# MPU-Peripherals.net
KiCad netlist of a schematic drawn in Altium Designer
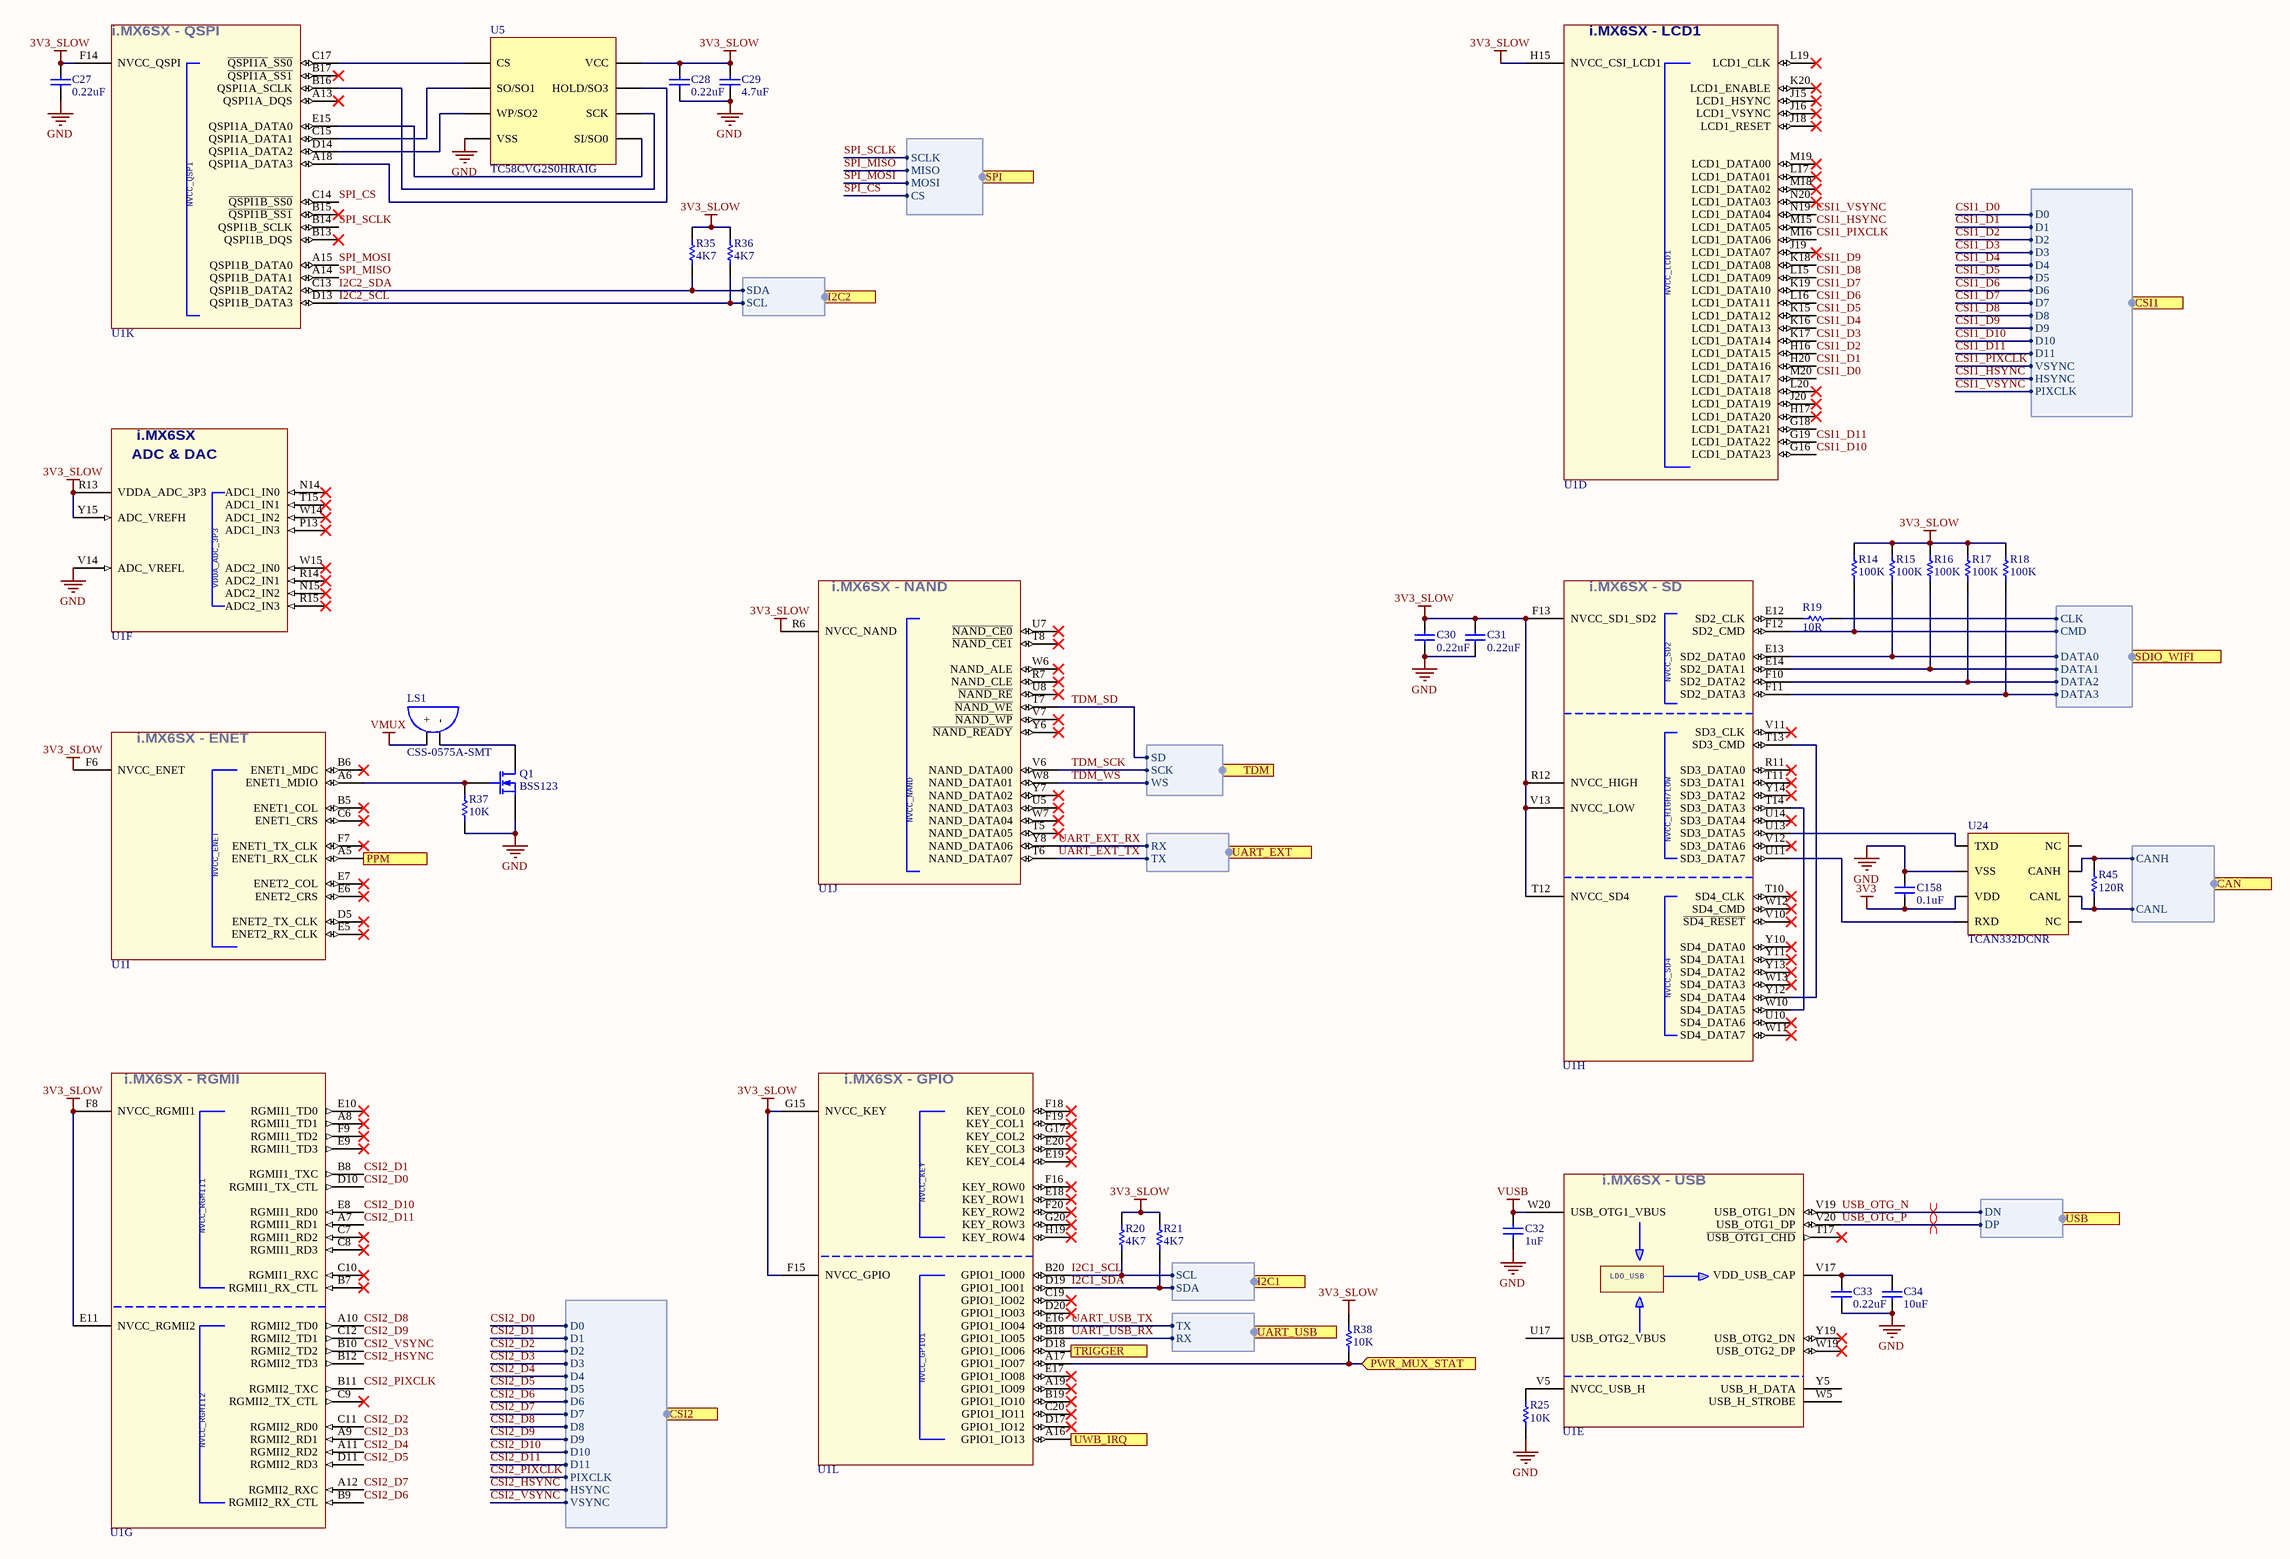
[diagram p0: MPU-Peripherals.SchDoc]

(export (version "E")
  (design (tool "Eeschema 10.0.6"))
  (components
    (comp (ref "C27")
      (value "0.22uF")
      (footprint "C0402[1005X55]")
      (description "0.22uF 6.3V 10% 0402 (1005 Metric)")
      (fields (field (name "PARTNUMBER") "JMK105BJ224KV-F") (field (name "MANUFACTURER") "Taiyo Yuden"))
      (libsource (lib "Capacitors") (part "CAP_0.22uF_6.3V_0402_10%"))
    )
    (comp (ref "C28")
      (value "0.22uF")
      (footprint "C0402[1005X55]")
      (description "0.22uF 6.3V 10% 0402 (1005 Metric)")
      (fields (field (name "PARTNUMBER") "JMK105BJ224KV-F") (field (name "MANUFACTURER") "Taiyo Yuden"))
      (libsource (lib "Capacitors") (part "CAP_0.22uF_6.3V_0402_10%"))
    )
    (comp (ref "C29")
      (value "4.7uF")
      (footprint "C0402[1005X55]")
      (description "4.7uF 6.3V 20% 0402 (1005 Metric)")
      (fields (field (name "PARTNUMBER") "GRM155R60J475ME47D") (field (name "MANUFACTURER") "Murata"))
      (libsource (lib "Capacitors") (part "CAP_4.7uF_6.3V_0402_20%"))
    )
    (comp (ref "C30")
      (value "0.22uF")
      (footprint "C0402[1005X55]")
      (description "0.22uF 6.3V 10% 0402 (1005 Metric)")
      (fields (field (name "PARTNUMBER") "JMK105BJ224KV-F") (field (name "MANUFACTURER") "Taiyo Yuden"))
      (libsource (lib "Capacitors") (part "CAP_0.22uF_6.3V_0402_10%"))
    )
    (comp (ref "C31")
      (value "0.22uF")
      (footprint "C0402[1005X55]")
      (description "0.22uF 6.3V 10% 0402 (1005 Metric)")
      (fields (field (name "PARTNUMBER") "JMK105BJ224KV-F") (field (name "MANUFACTURER") "Taiyo Yuden"))
      (libsource (lib "Capacitors") (part "CAP_0.22uF_6.3V_0402_10%"))
    )
    (comp (ref "C32")
      (value "1uF")
      (footprint "C0402[1005X55]")
      (description "1uF 16V 10% 0402 (1005 Metric)")
      (fields (field (name "PARTNUMBER") "GRM155R61C105KE01D") (field (name "MANUFACTURER") "Murata"))
      (libsource (lib "Capacitors") (part "CAP_1uF_16V_0402_10%"))
    )
    (comp (ref "C33")
      (value "0.22uF")
      (footprint "C0402[1005X55]")
      (description "0.22uF 6.3V 10% 0402 (1005 Metric)")
      (fields (field (name "PARTNUMBER") "JMK105BJ224KV-F") (field (name "MANUFACTURER") "Taiyo Yuden"))
      (libsource (lib "Capacitors") (part "CAP_0.22uF_6.3V_0402_10%"))
    )
    (comp (ref "C34")
      (value "10uF")
      (footprint "C0402[1005X55]")
      (description "10uF 6.3V 20% 0402 (1005 Metric)")
      (fields (field (name "PARTNUMBER") "GRM155R60J106ME44D") (field (name "MANUFACTURER") "Murata"))
      (libsource (lib "Capacitors") (part "CAP_10uF_6.3V_0402_20%"))
    )
    (comp (ref "C158")
      (value "0.1uF")
      (footprint "C0402[1005X55]")
      (description "0.1uF 6.3V 10% 0402 (1005 Metric)")
      (fields (field (name "PARTNUMBER") "GRM155R70J104KA01D") (field (name "MANUFACTURER") "Murata"))
      (libsource (lib "Capacitors") (part "CAP_0.1uF_6.3V_0402_10%"))
    )
    (comp (ref "LS1")
      (value "CSS-0575A-SMT")
      (footprint "CSS-0575A-SMT")
      (description "Magnetic Buzzer Transducer")
      (fields (field (name "MANUFACTURER") "CUI, Inc."))
      (libsource (lib "Components") (part "CSS-0575A-SMT"))
    )
    (comp (ref "Q1")
      (value "BSS123")
      (footprint "SOT323-3")
      (description "N-Channel MOSFET")
      (fields (field (name "PARTNUMBER") "BSS123WQ-7-F") (field (name "MANUFACTURER") "Diodes Incorporated"))
      (libsource (lib "MOSFETs") (part "BSS123WQ-7-F"))
    )
    (comp (ref "R14")
      (value "100K")
      (footprint "R0402[1005]")
      (description "100K 0.063W 1% 0402 (1005 Metric)")
      (fields (field (name "MANUFACTURER") "KOA Speer") (field (name "PARTNUMBER") "RK73H1ETTP1003F"))
      (libsource (lib "Resistors") (part "RES_100K_0402_1%"))
    )
    (comp (ref "R15")
      (value "100K")
      (footprint "R0402[1005]")
      (description "100K 0.063W 1% 0402 (1005 Metric)")
      (fields (field (name "MANUFACTURER") "KOA Speer") (field (name "PARTNUMBER") "RK73H1ETTP1003F"))
      (libsource (lib "Resistors") (part "RES_100K_0402_1%"))
    )
    (comp (ref "R16")
      (value "100K")
      (footprint "R0402[1005]")
      (description "100K 0.063W 1% 0402 (1005 Metric)")
      (fields (field (name "MANUFACTURER") "KOA Speer") (field (name "PARTNUMBER") "RK73H1ETTP1003F"))
      (libsource (lib "Resistors") (part "RES_100K_0402_1%"))
    )
    (comp (ref "R17")
      (value "100K")
      (footprint "R0402[1005]")
      (description "100K 0.063W 1% 0402 (1005 Metric)")
      (fields (field (name "MANUFACTURER") "KOA Speer") (field (name "PARTNUMBER") "RK73H1ETTP1003F"))
      (libsource (lib "Resistors") (part "RES_100K_0402_1%"))
    )
    (comp (ref "R18")
      (value "100K")
      (footprint "R0402[1005]")
      (description "100K 0.063W 1% 0402 (1005 Metric)")
      (fields (field (name "MANUFACTURER") "KOA Speer") (field (name "PARTNUMBER") "RK73H1ETTP1003F"))
      (libsource (lib "Resistors") (part "RES_100K_0402_1%"))
    )
    (comp (ref "R19")
      (value "10R")
      (footprint "R0402[1005]")
      (description "10R 0.063W 1% 0402 (1005 Metric)")
      (fields (field (name "MANUFACTURER") "KOA Speer") (field (name "PARTNUMBER") "RK73H1ETTP10R0F"))
      (libsource (lib "Resistors") (part "RES_10R_0402_1%"))
    )
    (comp (ref "R20")
      (value "4K7")
      (footprint "R0402[1005]")
      (description "4K7 0.063W 1% 0402 (1005 Metric)")
      (fields (field (name "MANUFACTURER") "KOA Speer") (field (name "PARTNUMBER") "RK73H1ETTP4701F"))
      (libsource (lib "Resistors") (part "RES_4K7_0402_1%"))
    )
    (comp (ref "R21")
      (value "4K7")
      (footprint "R0402[1005]")
      (description "4K7 0.063W 1% 0402 (1005 Metric)")
      (fields (field (name "MANUFACTURER") "KOA Speer") (field (name "PARTNUMBER") "RK73H1ETTP4701F"))
      (libsource (lib "Resistors") (part "RES_4K7_0402_1%"))
    )
    (comp (ref "R25")
      (value "10K")
      (footprint "R0402[1005]")
      (description "10K 0.063W 1% 0402 (1005 Metric)")
      (fields (field (name "MANUFACTURER") "KOA Speer") (field (name "PARTNUMBER") "RK73H1ETTP1002F"))
      (libsource (lib "Resistors") (part "RES_10K_0402_1%"))
    )
    (comp (ref "R35")
      (value "4K7")
      (footprint "R0402[1005]")
      (description "4K7 0.063W 1% 0402 (1005 Metric)")
      (fields (field (name "MANUFACTURER") "KOA Speer") (field (name "PARTNUMBER") "RK73H1ETTP4701F"))
      (libsource (lib "Resistors") (part "RES_4K7_0402_1%"))
    )
    (comp (ref "R36")
      (value "4K7")
      (footprint "R0402[1005]")
      (description "4K7 0.063W 1% 0402 (1005 Metric)")
      (fields (field (name "MANUFACTURER") "KOA Speer") (field (name "PARTNUMBER") "RK73H1ETTP4701F"))
      (libsource (lib "Resistors") (part "RES_4K7_0402_1%"))
    )
    (comp (ref "R37")
      (value "10K")
      (footprint "R0402[1005]")
      (description "10K 0.063W 1% 0402 (1005 Metric)")
      (fields (field (name "MANUFACTURER") "KOA Speer") (field (name "PARTNUMBER") "RK73H1ETTP1002F"))
      (libsource (lib "Resistors") (part "RES_10K_0402_1%"))
    )
    (comp (ref "R38")
      (value "10K")
      (footprint "R0402[1005]")
      (description "10K 0.063W 1% 0402 (1005 Metric)")
      (fields (field (name "MANUFACTURER") "KOA Speer") (field (name "PARTNUMBER") "RK73H1ETTP1002F"))
      (libsource (lib "Resistors") (part "RES_10K_0402_1%"))
    )
    (comp (ref "R45")
      (value "120R")
      (footprint "R0402[1005]")
      (description "120R 0.063W 1% 0402 (1005 Metric)")
      (fields (field (name "MANUFACTURER") "KOA Speer") (field (name "PARTNUMBER") "RK73H1ETTP1200F"))
      (libsource (lib "Resistors") (part "RES_120R_0402_1%"))
    )
    (comp (ref "U1")
      (value "MCIMX6X3EVO10AB")
      (footprint "BGA-400")
      (description "IC MPU I.MX6SX 1GHZ 400MAPBGA")
      (fields (field (name "MANUFACTURER") "NXP"))
      (libsource (lib "ICs") (part "MCIMX6X3EVO10AB"))
    )
    (comp (ref "U5")
      (value "TC58CVG2S0HRAIG")
      (footprint "WSON-8 (6X8MM)")
      (description "IC FLASH 4G SPI 104MHZ 8WSON")
      (fields (field (name "MANUFACTURER") "Toshiba Memory America, Inc."))
      (libsource (lib "ICs") (part "TC58CVG2S0HRAIG"))
    )
    (comp (ref "U24")
      (value "TCAN332DCNR")
      (footprint "SOT-23-8")
      (description "CAN Interface IC 3.3-V CAN Transceivers with CAN FD (Flexible Data Rate) 8-SOT-23 -40 to 125")
      (fields (field (name "MANUFACTURER") "Texas Instruments"))
      (libsource (lib "ICs") (part "TCAN332DCNR"))
    )
  )
  (nets
    (net (code "9") (name "/CANH") (class "Default")
      (node (ref "R45") (pin "2") (pinfunction "2_2") (pintype "passive"))
      (node (ref "U24") (pin "7") (pinfunction "CANH_7") (pintype "passive"))
    )
    (net (code "10") (name "/CANL") (class "Default")
      (node (ref "R45") (pin "1") (pinfunction "1_1") (pintype "passive"))
      (node (ref "U24") (pin "6") (pinfunction "CANL_6") (pintype "passive"))
    )
    (net (code "11") (name "/CLK") (class "Default")
      (node (ref "R19") (pin "2") (pinfunction "2_2") (pintype "passive"))
    )
    (net (code "12") (name "/CMD") (class "Default")
      (node (ref "R14") (pin "1") (pinfunction "1_1") (pintype "passive"))
      (node (ref "U1") (pin "F12") (pinfunction "SD2_CMD_F12") (pintype "bidirectional"))
    )
    (net (code "13") (name "/CSI1_D0") (class "Default")
      (node (ref "U1") (pin "M20") (pinfunction "LCD1_DATA17_M20") (pintype "bidirectional"))
    )
    (net (code "14") (name "/CSI1_D1") (class "Default")
      (node (ref "U1") (pin "H20") (pinfunction "LCD1_DATA16_H20") (pintype "bidirectional"))
    )
    (net (code "15") (name "/CSI1_D2") (class "Default")
      (node (ref "U1") (pin "H16") (pinfunction "LCD1_DATA15_H16") (pintype "bidirectional"))
    )
    (net (code "16") (name "/CSI1_D3") (class "Default")
      (node (ref "U1") (pin "K17") (pinfunction "LCD1_DATA14_K17") (pintype "bidirectional"))
    )
    (net (code "17") (name "/CSI1_D4") (class "Default")
      (node (ref "U1") (pin "K16") (pinfunction "LCD1_DATA13_K16") (pintype "bidirectional"))
    )
    (net (code "18") (name "/CSI1_D5") (class "Default")
      (node (ref "U1") (pin "K15") (pinfunction "LCD1_DATA12_K15") (pintype "bidirectional"))
    )
    (net (code "19") (name "/CSI1_D6") (class "Default")
      (node (ref "U1") (pin "L16") (pinfunction "LCD1_DATA11_L16") (pintype "bidirectional"))
    )
    (net (code "20") (name "/CSI1_D7") (class "Default")
      (node (ref "U1") (pin "K19") (pinfunction "LCD1_DATA10_K19") (pintype "bidirectional"))
    )
    (net (code "21") (name "/CSI1_D8") (class "Default")
      (node (ref "U1") (pin "L15") (pinfunction "LCD1_DATA09_L15") (pintype "bidirectional"))
    )
    (net (code "22") (name "/CSI1_D9") (class "Default")
      (node (ref "U1") (pin "K18") (pinfunction "LCD1_DATA08_K18") (pintype "bidirectional"))
    )
    (net (code "23") (name "/CSI1_D10") (class "Default")
      (node (ref "U1") (pin "G16") (pinfunction "LCD1_DATA23_G16") (pintype "bidirectional"))
    )
    (net (code "24") (name "/CSI1_D11") (class "Default")
      (node (ref "U1") (pin "G19") (pinfunction "LCD1_DATA22_G19") (pintype "bidirectional"))
    )
    (net (code "25") (name "/CSI1_HSYNC") (class "Default")
      (node (ref "U1") (pin "M15") (pinfunction "LCD1_DATA05_M15") (pintype "bidirectional"))
    )
    (net (code "26") (name "/CSI1_PIXCLK") (class "Default")
      (node (ref "U1") (pin "M16") (pinfunction "LCD1_DATA06_M16") (pintype "bidirectional"))
    )
    (net (code "27") (name "/CSI1_VSYNC") (class "Default")
      (node (ref "U1") (pin "N19") (pinfunction "LCD1_DATA04_N19") (pintype "bidirectional"))
    )
    (net (code "28") (name "/CSI2_D0") (class "Default")
      (node (ref "U1") (pin "D10") (pinfunction "RGMII1_TX_CTL_D10") (pintype "output"))
    )
    (net (code "29") (name "/CSI2_D1") (class "Default")
      (node (ref "U1") (pin "B8") (pinfunction "RGMII1_TXC_B8") (pintype "output"))
    )
    (net (code "30") (name "/CSI2_D2") (class "Default")
      (node (ref "U1") (pin "C11") (pinfunction "RGMII2_RD0_C11") (pintype "input"))
    )
    (net (code "31") (name "/CSI2_D3") (class "Default")
      (node (ref "U1") (pin "A9") (pinfunction "RGMII2_RD1_A9") (pintype "input"))
    )
    (net (code "32") (name "/CSI2_D4") (class "Default")
      (node (ref "U1") (pin "A11") (pinfunction "RGMII2_RD2_A11") (pintype "input"))
    )
    (net (code "33") (name "/CSI2_D5") (class "Default")
      (node (ref "U1") (pin "D11") (pinfunction "RGMII2_RD3_D11") (pintype "input"))
    )
    (net (code "34") (name "/CSI2_D6") (class "Default")
      (node (ref "U1") (pin "B9") (pinfunction "RGMII2_RX_CTL_B9") (pintype "input"))
    )
    (net (code "35") (name "/CSI2_D7") (class "Default")
      (node (ref "U1") (pin "A12") (pinfunction "RGMII2_RXC_A12") (pintype "input"))
    )
    (net (code "36") (name "/CSI2_D8") (class "Default")
      (node (ref "U1") (pin "A10") (pinfunction "RGMII2_TD0_A10") (pintype "output"))
    )
    (net (code "37") (name "/CSI2_D9") (class "Default")
      (node (ref "U1") (pin "C12") (pinfunction "RGMII2_TD1_C12") (pintype "output"))
    )
    (net (code "38") (name "/CSI2_D10") (class "Default")
      (node (ref "U1") (pin "E8") (pinfunction "RGMII1_RD0_E8") (pintype "input"))
    )
    (net (code "39") (name "/CSI2_D11") (class "Default")
      (node (ref "U1") (pin "A7") (pinfunction "RGMII1_RD1_A7") (pintype "input"))
    )
    (net (code "40") (name "/CSI2_HSYNC") (class "Default")
      (node (ref "U1") (pin "B12") (pinfunction "RGMII2_TD3_B12") (pintype "output"))
    )
    (net (code "41") (name "/CSI2_PIXCLK") (class "Default")
      (node (ref "U1") (pin "B11") (pinfunction "RGMII2_TXC_B11") (pintype "output"))
    )
    (net (code "42") (name "/CSI2_VSYNC") (class "Default")
      (node (ref "U1") (pin "B10") (pinfunction "RGMII2_TD2_B10") (pintype "output"))
    )
    (net (code "43") (name "/DATA0") (class "Default")
      (node (ref "R15") (pin "1") (pinfunction "1_1") (pintype "passive"))
      (node (ref "U1") (pin "E13") (pinfunction "SD2_DATA0_E13") (pintype "bidirectional"))
    )
    (net (code "44") (name "/DATA1") (class "Default")
      (node (ref "R16") (pin "1") (pinfunction "1_1") (pintype "passive"))
      (node (ref "U1") (pin "E14") (pinfunction "SD2_DATA1_E14") (pintype "bidirectional"))
    )
    (net (code "45") (name "/DATA2") (class "Default")
      (node (ref "R17") (pin "1") (pinfunction "1_1") (pintype "passive"))
      (node (ref "U1") (pin "F10") (pinfunction "SD2_DATA2_F10") (pintype "bidirectional"))
    )
    (net (code "46") (name "/DATA3") (class "Default")
      (node (ref "R18") (pin "1") (pinfunction "1_1") (pintype "passive"))
      (node (ref "U1") (pin "F11") (pinfunction "SD2_DATA3_F11") (pintype "bidirectional"))
    )
    (net (code "47") (name "/I2C1_SCL") (class "Default")
      (node (ref "R20") (pin "1") (pinfunction "1_1") (pintype "passive"))
      (node (ref "U1") (pin "B20") (pinfunction "GPIO1_IO00_B20") (pintype "bidirectional"))
    )
    (net (code "48") (name "/I2C1_SDA") (class "Default")
      (node (ref "R21") (pin "1") (pinfunction "1_1") (pintype "passive"))
      (node (ref "U1") (pin "D19") (pinfunction "GPIO1_IO01_D19") (pintype "bidirectional"))
    )
    (net (code "49") (name "/I2C2_SCL") (class "Default")
      (node (ref "R36") (pin "1") (pinfunction "1_1") (pintype "passive"))
      (node (ref "U1") (pin "D13") (pinfunction "QSPI1B_DATA3_D13") (pintype "bidirectional"))
    )
    (net (code "50") (name "/I2C2_SDA") (class "Default")
      (node (ref "R35") (pin "1") (pinfunction "1_1") (pintype "passive"))
      (node (ref "U1") (pin "C13") (pinfunction "QSPI1B_DATA2_C13") (pintype "bidirectional"))
    )
    (net (code "51") (name "/PPM") (class "Default")
      (node (ref "U1") (pin "A5") (pinfunction "ENET1_RX_CLK_A5") (pintype "bidirectional"))
    )
    (net (code "52") (name "/PWR_MUX_STAT") (class "Default")
      (node (ref "R38") (pin "1") (pinfunction "1_1") (pintype "passive"))
      (node (ref "U1") (pin "A17") (pinfunction "GPIO1_IO07_A17") (pintype "bidirectional"))
    )
    (net (code "53") (name "/SPI_CS") (class "Default")
      (node (ref "U1") (pin "C14") (pinfunction "~{QSPI1B_SS0}_C14") (pintype "bidirectional"))
    )
    (net (code "54") (name "/SPI_MISO") (class "Default")
      (node (ref "U1") (pin "A14") (pinfunction "QSPI1B_DATA1_A14") (pintype "bidirectional"))
    )
    (net (code "55") (name "/SPI_MOSI") (class "Default")
      (node (ref "U1") (pin "A15") (pinfunction "QSPI1B_DATA0_A15") (pintype "bidirectional"))
    )
    (net (code "56") (name "/SPI_SCLK") (class "Default")
      (node (ref "U1") (pin "B14") (pinfunction "QSPI1B_SCLK_B14") (pintype "bidirectional"))
    )
    (net (code "57") (name "/TDM_SCK") (class "Default")
      (node (ref "U1") (pin "V6") (pinfunction "NAND_DATA00_V6") (pintype "bidirectional"))
    )
    (net (code "58") (name "/TDM_SD") (class "Default")
      (node (ref "U1") (pin "T7") (pinfunction "~{NAND_WE}_T7") (pintype "bidirectional"))
    )
    (net (code "59") (name "/TDM_WS") (class "Default")
      (node (ref "U1") (pin "W8") (pinfunction "NAND_DATA01_W8") (pintype "bidirectional"))
    )
    (net (code "60") (name "/TRIGGER") (class "Default")
      (node (ref "U1") (pin "D18") (pinfunction "GPIO1_IO06_D18") (pintype "bidirectional"))
    )
    (net (code "61") (name "/UART_EXT_RX") (class "Default")
      (node (ref "U1") (pin "Y8") (pinfunction "NAND_DATA06_Y8") (pintype "bidirectional"))
    )
    (net (code "62") (name "/UART_EXT_TX") (class "Default")
      (node (ref "U1") (pin "T6") (pinfunction "NAND_DATA07_T6") (pintype "bidirectional"))
    )
    (net (code "63") (name "/UART_USB_RX") (class "Default")
      (node (ref "U1") (pin "B18") (pinfunction "GPIO1_IO05_B18") (pintype "bidirectional"))
    )
    (net (code "64") (name "/UART_USB_TX") (class "Default")
      (node (ref "U1") (pin "E16") (pinfunction "GPIO1_IO04_E16") (pintype "bidirectional"))
    )
    (net (code "65") (name "/USB_OTG_N") (class "Default")
      (node (ref "U1") (pin "V19") (pinfunction "USB_OTG1_DN_V19") (pintype "bidirectional"))
    )
    (net (code "66") (name "/USB_OTG_P") (class "Default")
      (node (ref "U1") (pin "V20") (pinfunction "USB_OTG1_DP_V20") (pintype "bidirectional"))
    )
    (net (code "67") (name "/UWB_IRQ") (class "Default")
      (node (ref "U1") (pin "A16") (pinfunction "GPIO1_IO13_A16") (pintype "bidirectional"))
    )
    (net (code "76") (name "3V3") (class "Default")
      (node (ref "C158") (pin "1") (pinfunction "1_1") (pintype "passive"))
      (node (ref "U24") (pin "3") (pinfunction "VDD_3") (pintype "passive"))
    )
    (net (code "77") (name "3V3_SLOW") (class "Default")
      (node (ref "C27") (pin "2") (pinfunction "2_2") (pintype "passive"))
      (node (ref "C28") (pin "2") (pinfunction "2_2") (pintype "passive"))
      (node (ref "C29") (pin "2") (pinfunction "2_2") (pintype "passive"))
      (node (ref "C30") (pin "2") (pinfunction "2_2") (pintype "passive"))
      (node (ref "C31") (pin "2") (pinfunction "2_2") (pintype "passive"))
      (node (ref "R14") (pin "2") (pinfunction "2_2") (pintype "passive"))
      (node (ref "R15") (pin "2") (pinfunction "2_2") (pintype "passive"))
      (node (ref "R16") (pin "2") (pinfunction "2_2") (pintype "passive"))
      (node (ref "R17") (pin "2") (pinfunction "2_2") (pintype "passive"))
      (node (ref "R18") (pin "2") (pinfunction "2_2") (pintype "passive"))
      (node (ref "R20") (pin "2") (pinfunction "2_2") (pintype "passive"))
      (node (ref "R21") (pin "2") (pinfunction "2_2") (pintype "passive"))
      (node (ref "R35") (pin "2") (pinfunction "2_2") (pintype "passive"))
      (node (ref "R36") (pin "2") (pinfunction "2_2") (pintype "passive"))
      (node (ref "R38") (pin "2") (pinfunction "2_2") (pintype "passive"))
      (node (ref "U1") (pin "E11") (pinfunction "NVCC_RGMII2_E11") (pintype "power_in"))
      (node (ref "U1") (pin "F13") (pinfunction "NVCC_SD1_SD2_F13") (pintype "power_in"))
      (node (ref "U1") (pin "F14") (pinfunction "NVCC_QSPI_F14") (pintype "power_in"))
      (node (ref "U1") (pin "F15") (pinfunction "NVCC_GPIO_F15") (pintype "power_in"))
      (node (ref "U1") (pin "F6") (pinfunction "NVCC_ENET_F6") (pintype "power_in"))
      (node (ref "U1") (pin "F8") (pinfunction "NVCC_RGMII1_F8") (pintype "power_in"))
      (node (ref "U1") (pin "G15") (pinfunction "NVCC_KEY_G15") (pintype "power_in"))
      (node (ref "U1") (pin "H15") (pinfunction "NVCC_CSI_LCD1_H15") (pintype "power_in"))
      (node (ref "U1") (pin "R12") (pinfunction "NVCC_HIGH_R12") (pintype "power_in"))
      (node (ref "U1") (pin "R13") (pinfunction "VDDA_ADC_3P3_R13") (pintype "power_in"))
      (node (ref "U1") (pin "R6") (pinfunction "NVCC_NAND_R6") (pintype "power_in"))
      (node (ref "U1") (pin "T12") (pinfunction "NVCC_SD4_T12") (pintype "power_in"))
      (node (ref "U1") (pin "V13") (pinfunction "NVCC_LOW_V13") (pintype "power_in"))
      (node (ref "U1") (pin "Y15") (pinfunction "ADC_VREFH_Y15") (pintype "input"))
      (node (ref "U5") (pin "8") (pinfunction "VCC_8") (pintype "passive"))
    )
    (net (code "78") (name "GND") (class "Default")
      (node (ref "C158") (pin "2") (pinfunction "2_2") (pintype "passive"))
      (node (ref "C27") (pin "1") (pinfunction "1_1") (pintype "passive"))
      (node (ref "C28") (pin "1") (pinfunction "1_1") (pintype "passive"))
      (node (ref "C29") (pin "1") (pinfunction "1_1") (pintype "passive"))
      (node (ref "C30") (pin "1") (pinfunction "1_1") (pintype "passive"))
      (node (ref "C31") (pin "1") (pinfunction "1_1") (pintype "passive"))
      (node (ref "C32") (pin "1") (pinfunction "1_1") (pintype "passive"))
      (node (ref "C33") (pin "1") (pinfunction "1_1") (pintype "passive"))
      (node (ref "C34") (pin "1") (pinfunction "1_1") (pintype "passive"))
      (node (ref "Q1") (pin "2") (pinfunction "S_2") (pintype "passive"))
      (node (ref "R25") (pin "1") (pinfunction "1_1") (pintype "passive"))
      (node (ref "R37") (pin "1") (pinfunction "1_1") (pintype "passive"))
      (node (ref "U1") (pin "V14") (pinfunction "ADC_VREFL_V14") (pintype "input"))
      (node (ref "U24") (pin "2") (pinfunction "VSS_2") (pintype "passive"))
      (node (ref "U5") (pin "4") (pinfunction "VSS_4") (pintype "passive"))
    )
    (net (code "79") (name "Net-(LS1--)") (class "Default")
      (node (ref "LS1") (pin "2") (pinfunction "-_2") (pintype "passive"))
      (node (ref "Q1") (pin "3") (pinfunction "D_3") (pintype "passive"))
    )
    (net (code "80") (name "Net-(Q1-G)") (class "Default")
      (node (ref "Q1") (pin "1") (pinfunction "G_1") (pintype "passive"))
      (node (ref "R37") (pin "2") (pinfunction "2_2") (pintype "passive"))
      (node (ref "U1") (pin "A6") (pinfunction "ENET1_MDIO_A6") (pintype "bidirectional"))
    )
    (net (code "81") (name "Net-(U1E-NVCC_USB_H)") (class "Default")
      (node (ref "R25") (pin "2") (pinfunction "2_2") (pintype "passive"))
      (node (ref "U1") (pin "V5") (pinfunction "NVCC_USB_H_V5") (pintype "power_in"))
    )
    (net (code "82") (name "Net-(U1E-VDD_USB_CAP)") (class "Default")
      (node (ref "C33") (pin "2") (pinfunction "2_2") (pintype "passive"))
      (node (ref "C34") (pin "2") (pinfunction "2_2") (pintype "passive"))
      (node (ref "U1") (pin "V17") (pinfunction "VDD_USB_CAP_V17") (pintype "power_in"))
    )
    (net (code "83") (name "Net-(U1H-SD2_CLK)") (class "Default")
      (node (ref "R19") (pin "1") (pinfunction "1_1") (pintype "passive"))
      (node (ref "U1") (pin "E12") (pinfunction "SD2_CLK_E12") (pintype "bidirectional"))
    )
    (net (code "84") (name "Net-(U1H-SD3_CMD)") (class "Default")
      (node (ref "U1") (pin "T13") (pinfunction "SD3_CMD_T13") (pintype "bidirectional"))
      (node (ref "U1") (pin "Y12") (pinfunction "SD4_DATA4_Y12") (pintype "bidirectional"))
    )
    (net (code "85") (name "Net-(U1H-SD3_DATA3)") (class "Default")
      (node (ref "U1") (pin "T14") (pinfunction "SD3_DATA3_T14") (pintype "bidirectional"))
      (node (ref "U1") (pin "W10") (pinfunction "SD4_DATA5_W10") (pintype "bidirectional"))
    )
    (net (code "86") (name "Net-(U1H-SD3_DATA5)") (class "Default")
      (node (ref "U1") (pin "U13") (pinfunction "SD3_DATA5_U13") (pintype "bidirectional"))
      (node (ref "U24") (pin "1") (pinfunction "TXD_1") (pintype "passive"))
    )
    (net (code "87") (name "Net-(U1H-SD3_DATA7)") (class "Default")
      (node (ref "U1") (pin "U11") (pinfunction "SD3_DATA7_U11") (pintype "bidirectional"))
      (node (ref "U24") (pin "4") (pinfunction "RXD_4") (pintype "passive"))
    )
    (net (code "88") (name "Net-(U1K-QSPI1A_DATA0)") (class "Default")
      (node (ref "U1") (pin "E15") (pinfunction "QSPI1A_DATA0_E15") (pintype "bidirectional"))
      (node (ref "U5") (pin "5") (pinfunction "SI/SO0_5") (pintype "power_in"))
    )
    (net (code "89") (name "Net-(U1K-QSPI1A_DATA1)") (class "Default")
      (node (ref "U1") (pin "C15") (pinfunction "QSPI1A_DATA1_C15") (pintype "bidirectional"))
      (node (ref "U5") (pin "2") (pinfunction "SO/SO1_2") (pintype "passive"))
    )
    (net (code "90") (name "Net-(U1K-QSPI1A_DATA2)") (class "Default")
      (node (ref "U1") (pin "D14") (pinfunction "QSPI1A_DATA2_D14") (pintype "bidirectional"))
      (node (ref "U5") (pin "3") (pinfunction "WP/SO2_3") (pintype "passive"))
    )
    (net (code "91") (name "Net-(U1K-QSPI1A_DATA3)") (class "Default")
      (node (ref "U1") (pin "A18") (pinfunction "QSPI1A_DATA3_A18") (pintype "bidirectional"))
      (node (ref "U5") (pin "7") (pinfunction "HOLD/SO3_7") (pintype "passive"))
    )
    (net (code "92") (name "Net-(U1K-QSPI1A_SCLK)") (class "Default")
      (node (ref "U1") (pin "B16") (pinfunction "QSPI1A_SCLK_B16") (pintype "bidirectional"))
      (node (ref "U5") (pin "6") (pinfunction "SCK_6") (pintype "passive"))
    )
    (net (code "93") (name "Net-(U1K-~{QSPI1A}_~{SS0})") (class "Default")
      (node (ref "U1") (pin "C17") (pinfunction "~{QSPI1A}_~{SS0}_C17") (pintype "bidirectional"))
      (node (ref "U5") (pin "1") (pinfunction "CS_1") (pintype "passive"))
    )
    (net (code "94") (name "VMUX") (class "Default")
      (node (ref "LS1") (pin "1") (pinfunction "+_1") (pintype "passive"))
    )
    (net (code "95") (name "VUSB") (class "Default")
      (node (ref "C32") (pin "2") (pinfunction "2_2") (pintype "passive"))
      (node (ref "U1") (pin "W20") (pinfunction "USB_OTG1_VBUS_W20") (pintype "power_in"))
    )
    (net (code "96") (name "unconnected-(U1D-LCD1_CLK-PadL19)") (class "Default")
      (node (ref "U1") (pin "L19") (pinfunction "LCD1_CLK_L19") (pintype "bidirectional+no_connect"))
    )
    (net (code "97") (name "unconnected-(U1D-LCD1_DATA00-PadM19)") (class "Default")
      (node (ref "U1") (pin "M19") (pinfunction "LCD1_DATA00_M19") (pintype "bidirectional+no_connect"))
    )
    (net (code "98") (name "unconnected-(U1D-LCD1_DATA01-PadL17)") (class "Default")
      (node (ref "U1") (pin "L17") (pinfunction "LCD1_DATA01_L17") (pintype "bidirectional+no_connect"))
    )
    (net (code "99") (name "unconnected-(U1D-LCD1_DATA02-PadM18)") (class "Default")
      (node (ref "U1") (pin "M18") (pinfunction "LCD1_DATA02_M18") (pintype "bidirectional+no_connect"))
    )
    (net (code "100") (name "unconnected-(U1D-LCD1_DATA03-PadN20)") (class "Default")
      (node (ref "U1") (pin "N20") (pinfunction "LCD1_DATA03_N20") (pintype "bidirectional+no_connect"))
    )
    (net (code "101") (name "unconnected-(U1D-LCD1_DATA07-PadJ19)") (class "Default")
      (node (ref "U1") (pin "J19") (pinfunction "LCD1_DATA07_J19") (pintype "bidirectional+no_connect"))
    )
    (net (code "102") (name "unconnected-(U1D-LCD1_DATA18-PadL20)") (class "Default")
      (node (ref "U1") (pin "L20") (pinfunction "LCD1_DATA18_L20") (pintype "bidirectional+no_connect"))
    )
    (net (code "103") (name "unconnected-(U1D-LCD1_DATA19-PadJ20)") (class "Default")
      (node (ref "U1") (pin "J20") (pinfunction "LCD1_DATA19_J20") (pintype "bidirectional+no_connect"))
    )
    (net (code "104") (name "unconnected-(U1D-LCD1_DATA20-PadH17)") (class "Default")
      (node (ref "U1") (pin "H17") (pinfunction "LCD1_DATA20_H17") (pintype "bidirectional+no_connect"))
    )
    (net (code "105") (name "unconnected-(U1D-LCD1_DATA21-PadG18)") (class "Default")
      (node (ref "U1") (pin "G18") (pinfunction "LCD1_DATA21_G18") (pintype "bidirectional"))
    )
    (net (code "106") (name "unconnected-(U1D-LCD1_ENABLE-PadK20)") (class "Default")
      (node (ref "U1") (pin "K20") (pinfunction "LCD1_ENABLE_K20") (pintype "bidirectional+no_connect"))
    )
    (net (code "107") (name "unconnected-(U1D-LCD1_HSYNC-PadJ15)") (class "Default")
      (node (ref "U1") (pin "J15") (pinfunction "LCD1_HSYNC_J15") (pintype "bidirectional+no_connect"))
    )
    (net (code "108") (name "unconnected-(U1D-LCD1_RESET-PadJ18)") (class "Default")
      (node (ref "U1") (pin "J18") (pinfunction "LCD1_RESET_J18") (pintype "bidirectional+no_connect"))
    )
    (net (code "109") (name "unconnected-(U1D-LCD1_VSYNC-PadJ16)") (class "Default")
      (node (ref "U1") (pin "J16") (pinfunction "LCD1_VSYNC_J16") (pintype "bidirectional+no_connect"))
    )
    (net (code "110") (name "unconnected-(U1E-USB_H_DATA-PadY5)") (class "Default")
      (node (ref "U1") (pin "Y5") (pinfunction "USB_H_DATA_Y5") (pintype "passive"))
    )
    (net (code "111") (name "unconnected-(U1E-USB_H_STROBE-PadW5)") (class "Default")
      (node (ref "U1") (pin "W5") (pinfunction "USB_H_STROBE_W5") (pintype "passive"))
    )
    (net (code "112") (name "unconnected-(U1E-USB_OTG2_DN-PadY19)") (class "Default")
      (node (ref "U1") (pin "Y19") (pinfunction "USB_OTG2_DN_Y19") (pintype "bidirectional+no_connect"))
    )
    (net (code "113") (name "unconnected-(U1E-USB_OTG2_DP-PadW19)") (class "Default")
      (node (ref "U1") (pin "W19") (pinfunction "USB_OTG2_DP_W19") (pintype "bidirectional+no_connect"))
    )
    (net (code "114") (name "unconnected-(U1E-USB_OTG2_VBUS-PadU17)") (class "Default")
      (node (ref "U1") (pin "U17") (pinfunction "USB_OTG2_VBUS_U17") (pintype "power_in"))
    )
    (net (code "115") (name "unconnected-(U1E-~{USB_OTG1_CHD}-PadT17)") (class "Default")
      (node (ref "U1") (pin "T17") (pinfunction "~{USB_OTG1_CHD}_T17") (pintype "output+no_connect"))
    )
    (net (code "116") (name "unconnected-(U1F-ADC1_IN0-PadN14)") (class "Default")
      (node (ref "U1") (pin "N14") (pinfunction "ADC1_IN0_N14") (pintype "input+no_connect"))
    )
    (net (code "117") (name "unconnected-(U1F-ADC1_IN1-PadT15)") (class "Default")
      (node (ref "U1") (pin "T15") (pinfunction "ADC1_IN1_T15") (pintype "input+no_connect"))
    )
    (net (code "118") (name "unconnected-(U1F-ADC1_IN2-PadW14)") (class "Default")
      (node (ref "U1") (pin "W14") (pinfunction "ADC1_IN2_W14") (pintype "input+no_connect"))
    )
    (net (code "119") (name "unconnected-(U1F-ADC1_IN3-PadP13)") (class "Default")
      (node (ref "U1") (pin "P13") (pinfunction "ADC1_IN3_P13") (pintype "input+no_connect"))
    )
    (net (code "120") (name "unconnected-(U1F-ADC2_IN0-PadW15)") (class "Default")
      (node (ref "U1") (pin "W15") (pinfunction "ADC2_IN0_W15") (pintype "input+no_connect"))
    )
    (net (code "121") (name "unconnected-(U1F-ADC2_IN1-PadR14)") (class "Default")
      (node (ref "U1") (pin "R14") (pinfunction "ADC2_IN1_R14") (pintype "input+no_connect"))
    )
    (net (code "122") (name "unconnected-(U1F-ADC2_IN2-PadN15)") (class "Default")
      (node (ref "U1") (pin "N15") (pinfunction "ADC2_IN2_N15") (pintype "input+no_connect"))
    )
    (net (code "123") (name "unconnected-(U1F-ADC2_IN3-PadR15)") (class "Default")
      (node (ref "U1") (pin "R15") (pinfunction "ADC2_IN3_R15") (pintype "input+no_connect"))
    )
    (net (code "124") (name "unconnected-(U1G-RGMII1_RD2-PadC7)") (class "Default")
      (node (ref "U1") (pin "C7") (pinfunction "RGMII1_RD2_C7") (pintype "input+no_connect"))
    )
    (net (code "125") (name "unconnected-(U1G-RGMII1_RD3-PadC8)") (class "Default")
      (node (ref "U1") (pin "C8") (pinfunction "RGMII1_RD3_C8") (pintype "input+no_connect"))
    )
    (net (code "126") (name "unconnected-(U1G-RGMII1_RXC-PadC10)") (class "Default")
      (node (ref "U1") (pin "C10") (pinfunction "RGMII1_RXC_C10") (pintype "input+no_connect"))
    )
    (net (code "127") (name "unconnected-(U1G-RGMII1_RX_CTL-PadB7)") (class "Default")
      (node (ref "U1") (pin "B7") (pinfunction "RGMII1_RX_CTL_B7") (pintype "input+no_connect"))
    )
    (net (code "128") (name "unconnected-(U1G-RGMII1_TD0-PadE10)") (class "Default")
      (node (ref "U1") (pin "E10") (pinfunction "RGMII1_TD0_E10") (pintype "output+no_connect"))
    )
    (net (code "129") (name "unconnected-(U1G-RGMII1_TD1-PadA8)") (class "Default")
      (node (ref "U1") (pin "A8") (pinfunction "RGMII1_TD1_A8") (pintype "output+no_connect"))
    )
    (net (code "130") (name "unconnected-(U1G-RGMII1_TD2-PadF9)") (class "Default")
      (node (ref "U1") (pin "F9") (pinfunction "RGMII1_TD2_F9") (pintype "output+no_connect"))
    )
    (net (code "131") (name "unconnected-(U1G-RGMII1_TD3-PadE9)") (class "Default")
      (node (ref "U1") (pin "E9") (pinfunction "RGMII1_TD3_E9") (pintype "output+no_connect"))
    )
    (net (code "132") (name "unconnected-(U1G-RGMII2_TX_CTL-PadC9)") (class "Default")
      (node (ref "U1") (pin "C9") (pinfunction "RGMII2_TX_CTL_C9") (pintype "output+no_connect"))
    )
    (net (code "133") (name "unconnected-(U1H-SD3_CLK-PadV11)") (class "Default")
      (node (ref "U1") (pin "V11") (pinfunction "SD3_CLK_V11") (pintype "bidirectional+no_connect"))
    )
    (net (code "134") (name "unconnected-(U1H-SD3_DATA0-PadR11)") (class "Default")
      (node (ref "U1") (pin "R11") (pinfunction "SD3_DATA0_R11") (pintype "bidirectional+no_connect"))
    )
    (net (code "135") (name "unconnected-(U1H-SD3_DATA1-PadT11)") (class "Default")
      (node (ref "U1") (pin "T11") (pinfunction "SD3_DATA1_T11") (pintype "bidirectional+no_connect"))
    )
    (net (code "136") (name "unconnected-(U1H-SD3_DATA2-PadY14)") (class "Default")
      (node (ref "U1") (pin "Y14") (pinfunction "SD3_DATA2_Y14") (pintype "bidirectional+no_connect"))
    )
    (net (code "137") (name "unconnected-(U1H-SD3_DATA4-PadU14)") (class "Default")
      (node (ref "U1") (pin "U14") (pinfunction "SD3_DATA4_U14") (pintype "bidirectional+no_connect"))
    )
    (net (code "138") (name "unconnected-(U1H-SD3_DATA6-PadV12)") (class "Default")
      (node (ref "U1") (pin "V12") (pinfunction "SD3_DATA6_V12") (pintype "bidirectional+no_connect"))
    )
    (net (code "139") (name "unconnected-(U1H-SD4_CLK-PadT10)") (class "Default")
      (node (ref "U1") (pin "T10") (pinfunction "SD4_CLK_T10") (pintype "bidirectional+no_connect"))
    )
    (net (code "140") (name "unconnected-(U1H-SD4_CMD-PadW12)") (class "Default")
      (node (ref "U1") (pin "W12") (pinfunction "SD4_CMD_W12") (pintype "bidirectional+no_connect"))
    )
    (net (code "141") (name "unconnected-(U1H-SD4_DATA0-PadY10)") (class "Default")
      (node (ref "U1") (pin "Y10") (pinfunction "SD4_DATA0_Y10") (pintype "bidirectional+no_connect"))
    )
    (net (code "142") (name "unconnected-(U1H-SD4_DATA1-PadY11)") (class "Default")
      (node (ref "U1") (pin "Y11") (pinfunction "SD4_DATA1_Y11") (pintype "bidirectional+no_connect"))
    )
    (net (code "143") (name "unconnected-(U1H-SD4_DATA2-PadY13)") (class "Default")
      (node (ref "U1") (pin "Y13") (pinfunction "SD4_DATA2_Y13") (pintype "bidirectional+no_connect"))
    )
    (net (code "144") (name "unconnected-(U1H-SD4_DATA3-PadW13)") (class "Default")
      (node (ref "U1") (pin "W13") (pinfunction "SD4_DATA3_W13") (pintype "bidirectional+no_connect"))
    )
    (net (code "145") (name "unconnected-(U1H-SD4_DATA6-PadU10)") (class "Default")
      (node (ref "U1") (pin "U10") (pinfunction "SD4_DATA6_U10") (pintype "bidirectional+no_connect"))
    )
    (net (code "146") (name "unconnected-(U1H-SD4_DATA7-PadW11)") (class "Default")
      (node (ref "U1") (pin "W11") (pinfunction "SD4_DATA7_W11") (pintype "bidirectional+no_connect"))
    )
    (net (code "147") (name "unconnected-(U1H-~{SD4_RESET}-PadV10)") (class "Default")
      (node (ref "U1") (pin "V10") (pinfunction "~{SD4_RESET}_V10") (pintype "bidirectional+no_connect"))
    )
    (net (code "148") (name "unconnected-(U1I-ENET1_COL-PadB5)") (class "Default")
      (node (ref "U1") (pin "B5") (pinfunction "ENET1_COL_B5") (pintype "bidirectional+no_connect"))
    )
    (net (code "149") (name "unconnected-(U1I-ENET1_CRS-PadC6)") (class "Default")
      (node (ref "U1") (pin "C6") (pinfunction "ENET1_CRS_C6") (pintype "bidirectional+no_connect"))
    )
    (net (code "150") (name "unconnected-(U1I-ENET1_MDC-PadB6)") (class "Default")
      (node (ref "U1") (pin "B6") (pinfunction "ENET1_MDC_B6") (pintype "bidirectional+no_connect"))
    )
    (net (code "151") (name "unconnected-(U1I-ENET1_TX_CLK-PadF7)") (class "Default")
      (node (ref "U1") (pin "F7") (pinfunction "ENET1_TX_CLK_F7") (pintype "bidirectional+no_connect"))
    )
    (net (code "152") (name "unconnected-(U1I-ENET2_COL-PadE7)") (class "Default")
      (node (ref "U1") (pin "E7") (pinfunction "ENET2_COL_E7") (pintype "bidirectional+no_connect"))
    )
    (net (code "153") (name "unconnected-(U1I-ENET2_CRS-PadE6)") (class "Default")
      (node (ref "U1") (pin "E6") (pinfunction "ENET2_CRS_E6") (pintype "bidirectional+no_connect"))
    )
    (net (code "154") (name "unconnected-(U1I-ENET2_RX_CLK-PadE5)") (class "Default")
      (node (ref "U1") (pin "E5") (pinfunction "ENET2_RX_CLK_E5") (pintype "bidirectional+no_connect"))
    )
    (net (code "155") (name "unconnected-(U1I-ENET2_TX_CLK-PadD5)") (class "Default")
      (node (ref "U1") (pin "D5") (pinfunction "ENET2_TX_CLK_D5") (pintype "bidirectional+no_connect"))
    )
    (net (code "156") (name "unconnected-(U1J-NAND_ALE-PadW6)") (class "Default")
      (node (ref "U1") (pin "W6") (pinfunction "NAND_ALE_W6") (pintype "bidirectional+no_connect"))
    )
    (net (code "157") (name "unconnected-(U1J-NAND_CLE-PadR7)") (class "Default")
      (node (ref "U1") (pin "R7") (pinfunction "NAND_CLE_R7") (pintype "bidirectional+no_connect"))
    )
    (net (code "158") (name "unconnected-(U1J-NAND_DATA02-PadY7)") (class "Default")
      (node (ref "U1") (pin "Y7") (pinfunction "NAND_DATA02_Y7") (pintype "bidirectional+no_connect"))
    )
    (net (code "159") (name "unconnected-(U1J-NAND_DATA03-PadU5)") (class "Default")
      (node (ref "U1") (pin "U5") (pinfunction "NAND_DATA03_U5") (pintype "bidirectional+no_connect"))
    )
    (net (code "160") (name "unconnected-(U1J-NAND_DATA04-PadW7)") (class "Default")
      (node (ref "U1") (pin "W7") (pinfunction "NAND_DATA04_W7") (pintype "bidirectional+no_connect"))
    )
    (net (code "161") (name "unconnected-(U1J-NAND_DATA05-PadT5)") (class "Default")
      (node (ref "U1") (pin "T5") (pinfunction "NAND_DATA05_T5") (pintype "bidirectional+no_connect"))
    )
    (net (code "162") (name "unconnected-(U1J-~{NAND_CE0}-PadU7)") (class "Default")
      (node (ref "U1") (pin "U7") (pinfunction "~{NAND_CE0}_U7") (pintype "bidirectional+no_connect"))
    )
    (net (code "163") (name "unconnected-(U1J-~{NAND_CE1}-PadT8)") (class "Default")
      (node (ref "U1") (pin "T8") (pinfunction "~{NAND_CE1}_T8") (pintype "bidirectional+no_connect"))
    )
    (net (code "164") (name "unconnected-(U1J-~{NAND_READY}-PadY6)") (class "Default")
      (node (ref "U1") (pin "Y6") (pinfunction "~{NAND_READY}_Y6") (pintype "bidirectional+no_connect"))
    )
    (net (code "165") (name "unconnected-(U1J-~{NAND_RE}-PadU8)") (class "Default")
      (node (ref "U1") (pin "U8") (pinfunction "~{NAND_RE}_U8") (pintype "bidirectional+no_connect"))
    )
    (net (code "166") (name "unconnected-(U1J-~{NAND_WP}-PadV7)") (class "Default")
      (node (ref "U1") (pin "V7") (pinfunction "~{NAND_WP}_V7") (pintype "bidirectional+no_connect"))
    )
    (net (code "167") (name "unconnected-(U1K-QSPI1A_DQS-PadA13)") (class "Default")
      (node (ref "U1") (pin "A13") (pinfunction "QSPI1A_DQS_A13") (pintype "bidirectional+no_connect"))
    )
    (net (code "168") (name "unconnected-(U1K-QSPI1B_DQS-PadB13)") (class "Default")
      (node (ref "U1") (pin "B13") (pinfunction "QSPI1B_DQS_B13") (pintype "bidirectional+no_connect"))
    )
    (net (code "169") (name "unconnected-(U1K-~{QSPI1A_SS1}-PadB17)") (class "Default")
      (node (ref "U1") (pin "B17") (pinfunction "~{QSPI1A_SS1}_B17") (pintype "bidirectional+no_connect"))
    )
    (net (code "170") (name "unconnected-(U1K-~{QSPI1B_SS1}-PadB15)") (class "Default")
      (node (ref "U1") (pin "B15") (pinfunction "~{QSPI1B_SS1}_B15") (pintype "bidirectional+no_connect"))
    )
    (net (code "171") (name "unconnected-(U1L-GPIO1_IO02-PadC19)") (class "Default")
      (node (ref "U1") (pin "C19") (pinfunction "GPIO1_IO02_C19") (pintype "bidirectional+no_connect"))
    )
    (net (code "172") (name "unconnected-(U1L-GPIO1_IO03-PadD20)") (class "Default")
      (node (ref "U1") (pin "D20") (pinfunction "GPIO1_IO03_D20") (pintype "bidirectional+no_connect"))
    )
    (net (code "173") (name "unconnected-(U1L-GPIO1_IO08-PadE17)") (class "Default")
      (node (ref "U1") (pin "E17") (pinfunction "GPIO1_IO08_E17") (pintype "bidirectional+no_connect"))
    )
    (net (code "174") (name "unconnected-(U1L-GPIO1_IO09-PadA19)") (class "Default")
      (node (ref "U1") (pin "A19") (pinfunction "GPIO1_IO09_A19") (pintype "bidirectional+no_connect"))
    )
    (net (code "175") (name "unconnected-(U1L-GPIO1_IO10-PadB19)") (class "Default")
      (node (ref "U1") (pin "B19") (pinfunction "GPIO1_IO10_B19") (pintype "bidirectional+no_connect"))
    )
    (net (code "176") (name "unconnected-(U1L-GPIO1_IO11-PadC20)") (class "Default")
      (node (ref "U1") (pin "C20") (pinfunction "GPIO1_IO11_C20") (pintype "bidirectional+no_connect"))
    )
    (net (code "177") (name "unconnected-(U1L-GPIO1_IO12-PadD17)") (class "Default")
      (node (ref "U1") (pin "D17") (pinfunction "GPIO1_IO12_D17") (pintype "bidirectional+no_connect"))
    )
    (net (code "178") (name "unconnected-(U1L-KEY_COL0-PadF18)") (class "Default")
      (node (ref "U1") (pin "F18") (pinfunction "KEY_COL0_F18") (pintype "bidirectional+no_connect"))
    )
    (net (code "179") (name "unconnected-(U1L-KEY_COL1-PadF19)") (class "Default")
      (node (ref "U1") (pin "F19") (pinfunction "KEY_COL1_F19") (pintype "bidirectional+no_connect"))
    )
    (net (code "180") (name "unconnected-(U1L-KEY_COL2-PadG17)") (class "Default")
      (node (ref "U1") (pin "G17") (pinfunction "KEY_COL2_G17") (pintype "bidirectional+no_connect"))
    )
    (net (code "181") (name "unconnected-(U1L-KEY_COL3-PadE20)") (class "Default")
      (node (ref "U1") (pin "E20") (pinfunction "KEY_COL3_E20") (pintype "bidirectional+no_connect"))
    )
    (net (code "182") (name "unconnected-(U1L-KEY_COL4-PadE19)") (class "Default")
      (node (ref "U1") (pin "E19") (pinfunction "KEY_COL4_E19") (pintype "bidirectional+no_connect"))
    )
    (net (code "183") (name "unconnected-(U1L-KEY_ROW0-PadF16)") (class "Default")
      (node (ref "U1") (pin "F16") (pinfunction "KEY_ROW0_F16") (pintype "bidirectional+no_connect"))
    )
    (net (code "184") (name "unconnected-(U1L-KEY_ROW1-PadE18)") (class "Default")
      (node (ref "U1") (pin "E18") (pinfunction "KEY_ROW1_E18") (pintype "bidirectional+no_connect"))
    )
    (net (code "185") (name "unconnected-(U1L-KEY_ROW2-PadF20)") (class "Default")
      (node (ref "U1") (pin "F20") (pinfunction "KEY_ROW2_F20") (pintype "bidirectional+no_connect"))
    )
    (net (code "186") (name "unconnected-(U1L-KEY_ROW3-PadG20)") (class "Default")
      (node (ref "U1") (pin "G20") (pinfunction "KEY_ROW3_G20") (pintype "bidirectional+no_connect"))
    )
    (net (code "187") (name "unconnected-(U1L-KEY_ROW4-PadH19)") (class "Default")
      (node (ref "U1") (pin "H19") (pinfunction "KEY_ROW4_H19") (pintype "bidirectional+no_connect"))
    )
    (net (code "188") (name "unconnected-(U24-NC-Pad5)") (class "Default")
      (node (ref "U24") (pin "5") (pinfunction "NC_5") (pintype "passive"))
    )
    (net (code "189") (name "unconnected-(U24-NC-Pad8)") (class "Default")
      (node (ref "U24") (pin "8") (pinfunction "NC_8") (pintype "passive"))
    )
  )
)
